# 05_Seven_Seg.net
KiCad netlist of a schematic drawn in Altium Designer
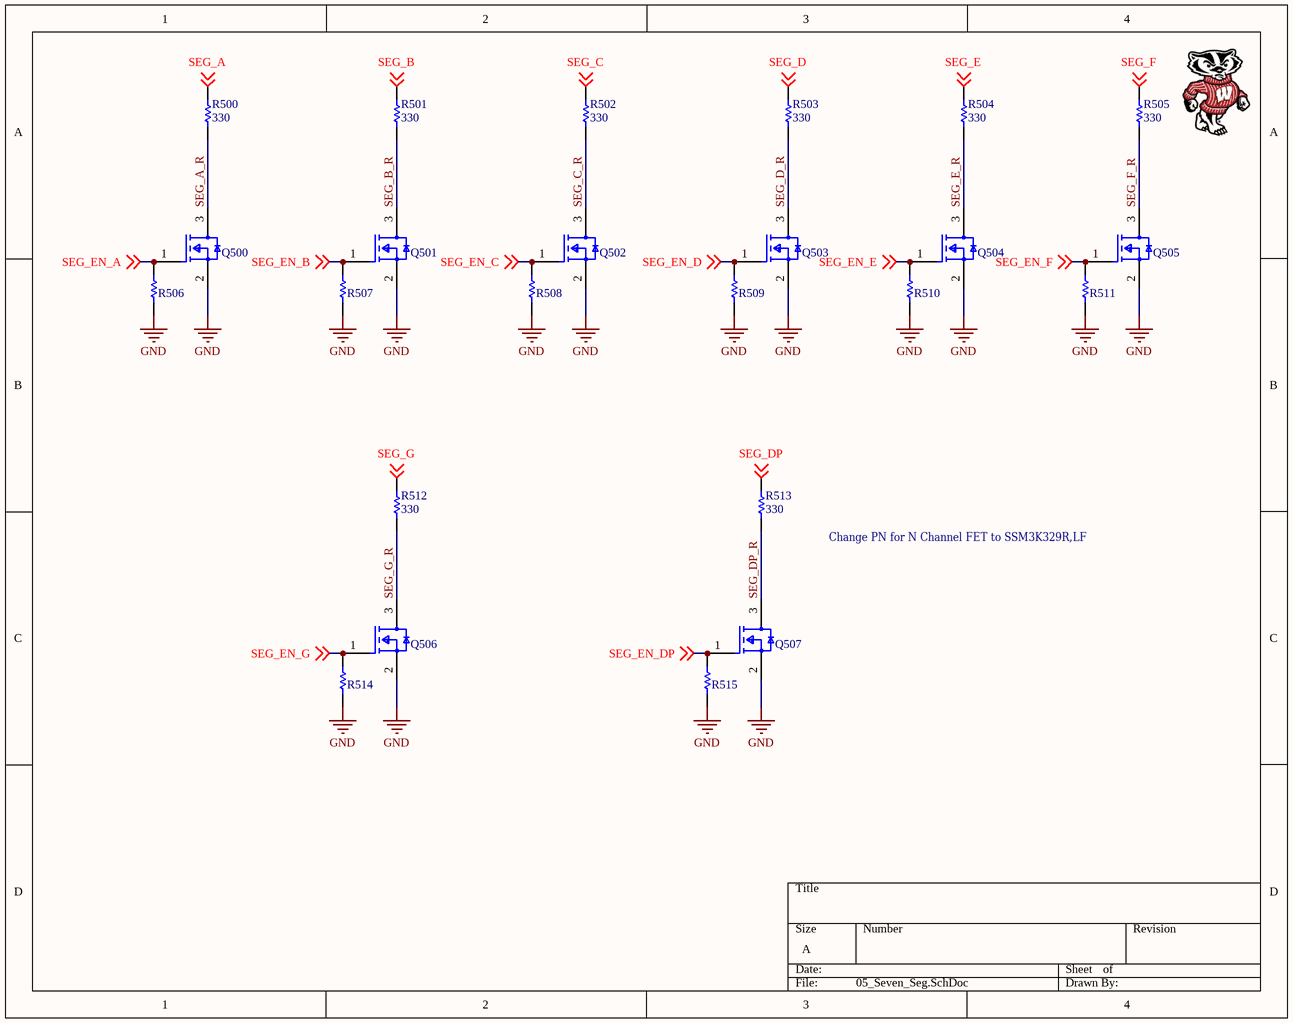
[diagram p0: 05_Seven_Seg.SchDoc]

(export (version "E")
  (design (tool "Eeschema 10.0.6"))
  (components
    (comp (ref "Q500")
      (value "NDS7002A")
      (footprint "Diodes_Inc_SOT23_IPC_A")
      (description "FAIRCHILD SEMICONDUCTOR         NDS7002A.            MOSFET, FULL REEL")
      (fields (field (name "VOLTAGE") "60V"))
      (libsource (lib "Transistors") (part "NDS7002A"))
    )
    (comp (ref "Q501")
      (value "NDS7002A")
      (footprint "Diodes_Inc_SOT23_IPC_A")
      (description "FAIRCHILD SEMICONDUCTOR         NDS7002A.            MOSFET, FULL REEL")
      (fields (field (name "VOLTAGE") "60V"))
      (libsource (lib "Transistors") (part "NDS7002A"))
    )
    (comp (ref "Q502")
      (value "NDS7002A")
      (footprint "Diodes_Inc_SOT23_IPC_A")
      (description "FAIRCHILD SEMICONDUCTOR         NDS7002A.            MOSFET, FULL REEL")
      (fields (field (name "VOLTAGE") "60V"))
      (libsource (lib "Transistors") (part "NDS7002A"))
    )
    (comp (ref "Q503")
      (value "NDS7002A")
      (footprint "Diodes_Inc_SOT23_IPC_A")
      (description "FAIRCHILD SEMICONDUCTOR         NDS7002A.            MOSFET, FULL REEL")
      (fields (field (name "VOLTAGE") "60V"))
      (libsource (lib "Transistors") (part "NDS7002A"))
    )
    (comp (ref "Q504")
      (value "NDS7002A")
      (footprint "Diodes_Inc_SOT23_IPC_A")
      (description "FAIRCHILD SEMICONDUCTOR         NDS7002A.            MOSFET, FULL REEL")
      (fields (field (name "VOLTAGE") "60V"))
      (libsource (lib "Transistors") (part "NDS7002A"))
    )
    (comp (ref "Q505")
      (value "NDS7002A")
      (footprint "Diodes_Inc_SOT23_IPC_A")
      (description "FAIRCHILD SEMICONDUCTOR         NDS7002A.            MOSFET, FULL REEL")
      (fields (field (name "VOLTAGE") "60V"))
      (libsource (lib "Transistors") (part "NDS7002A"))
    )
    (comp (ref "Q506")
      (value "NDS7002A")
      (footprint "Diodes_Inc_SOT23_IPC_A")
      (description "FAIRCHILD SEMICONDUCTOR         NDS7002A.            MOSFET, FULL REEL")
      (fields (field (name "VOLTAGE") "60V"))
      (libsource (lib "Transistors") (part "NDS7002A"))
    )
    (comp (ref "Q507")
      (value "NDS7002A")
      (footprint "Diodes_Inc_SOT23_IPC_A")
      (description "FAIRCHILD SEMICONDUCTOR         NDS7002A.            MOSFET, FULL REEL")
      (fields (field (name "VOLTAGE") "60V"))
      (libsource (lib "Transistors") (part "NDS7002A"))
    )
    (comp (ref "R500")
      (value "330")
      (footprint "RES_0805")
      (description "RES 330 OHM 1% 1/8W 0805")
      (fields (field (name "TOLERANCE") "1%"))
      (libsource (lib "Resistors") (part "RES_0805_R_330.00"))
    )
    (comp (ref "R501")
      (value "330")
      (footprint "RES_0805")
      (description "RES 330 OHM 1% 1/8W 0805")
      (fields (field (name "TOLERANCE") "1%"))
      (libsource (lib "Resistors") (part "RES_0805_R_330.00"))
    )
    (comp (ref "R502")
      (value "330")
      (footprint "RES_0805")
      (description "RES 330 OHM 1% 1/8W 0805")
      (fields (field (name "TOLERANCE") "1%"))
      (libsource (lib "Resistors") (part "RES_0805_R_330.00"))
    )
    (comp (ref "R503")
      (value "330")
      (footprint "RES_0805")
      (description "RES 330 OHM 1% 1/8W 0805")
      (fields (field (name "TOLERANCE") "1%"))
      (libsource (lib "Resistors") (part "RES_0805_R_330.00"))
    )
    (comp (ref "R504")
      (value "330")
      (footprint "RES_0805")
      (description "RES 330 OHM 1% 1/8W 0805")
      (fields (field (name "TOLERANCE") "1%"))
      (libsource (lib "Resistors") (part "RES_0805_R_330.00"))
    )
    (comp (ref "R505")
      (value "330")
      (footprint "RES_0805")
      (description "RES 330 OHM 1% 1/8W 0805")
      (fields (field (name "TOLERANCE") "1%"))
      (libsource (lib "Resistors") (part "RES_0805_R_330.00"))
    )
    (comp (ref "R506")
      (value "RES_0805_K_010.00")
      (footprint "RES_0805")
      (description "RES SMD 10K OHM 1% 1/8W 0805")
      (fields (field (name "TOLERANCE") "1%"))
      (libsource (lib "Resistors") (part "RES_0805_K_010.00"))
    )
    (comp (ref "R507")
      (value "RES_0805_K_010.00")
      (footprint "RES_0805")
      (description "RES SMD 10K OHM 1% 1/8W 0805")
      (fields (field (name "TOLERANCE") "1%"))
      (libsource (lib "Resistors") (part "RES_0805_K_010.00"))
    )
    (comp (ref "R508")
      (value "RES_0805_K_010.00")
      (footprint "RES_0805")
      (description "RES SMD 10K OHM 1% 1/8W 0805")
      (fields (field (name "TOLERANCE") "1%"))
      (libsource (lib "Resistors") (part "RES_0805_K_010.00"))
    )
    (comp (ref "R509")
      (value "RES_0805_K_010.00")
      (footprint "RES_0805")
      (description "RES SMD 10K OHM 1% 1/8W 0805")
      (fields (field (name "TOLERANCE") "1%"))
      (libsource (lib "Resistors") (part "RES_0805_K_010.00"))
    )
    (comp (ref "R510")
      (value "RES_0805_K_010.00")
      (footprint "RES_0805")
      (description "RES SMD 10K OHM 1% 1/8W 0805")
      (fields (field (name "TOLERANCE") "1%"))
      (libsource (lib "Resistors") (part "RES_0805_K_010.00"))
    )
    (comp (ref "R511")
      (value "RES_0805_K_010.00")
      (footprint "RES_0805")
      (description "RES SMD 10K OHM 1% 1/8W 0805")
      (fields (field (name "TOLERANCE") "1%"))
      (libsource (lib "Resistors") (part "RES_0805_K_010.00"))
    )
    (comp (ref "R512")
      (value "330")
      (footprint "RES_0805")
      (description "RES 330 OHM 1% 1/8W 0805")
      (fields (field (name "TOLERANCE") "1%"))
      (libsource (lib "Resistors") (part "RES_0805_R_330.00"))
    )
    (comp (ref "R513")
      (value "330")
      (footprint "RES_0805")
      (description "RES 330 OHM 1% 1/8W 0805")
      (fields (field (name "TOLERANCE") "1%"))
      (libsource (lib "Resistors") (part "RES_0805_R_330.00"))
    )
    (comp (ref "R514")
      (value "RES_0805_K_010.00")
      (footprint "RES_0805")
      (description "RES SMD 10K OHM 1% 1/8W 0805")
      (fields (field (name "TOLERANCE") "1%"))
      (libsource (lib "Resistors") (part "RES_0805_K_010.00"))
    )
    (comp (ref "R515")
      (value "RES_0805_K_010.00")
      (footprint "RES_0805")
      (description "RES SMD 10K OHM 1% 1/8W 0805")
      (fields (field (name "TOLERANCE") "1%"))
      (libsource (lib "Resistors") (part "RES_0805_K_010.00"))
    )
  )
  (nets
    (net (code "1") (name "/SEG_A_R") (class "Default")
      (node (ref "Q500") (pin "3") (pinfunction "D_3") (pintype "passive"))
      (node (ref "R500") (pin "1") (pinfunction "1_1") (pintype "passive"))
    )
    (net (code "2") (name "/SEG_B_R") (class "Default")
      (node (ref "Q501") (pin "3") (pinfunction "D_3") (pintype "passive"))
      (node (ref "R501") (pin "1") (pinfunction "1_1") (pintype "passive"))
    )
    (net (code "3") (name "/SEG_C_R") (class "Default")
      (node (ref "Q502") (pin "3") (pinfunction "D_3") (pintype "passive"))
      (node (ref "R502") (pin "1") (pinfunction "1_1") (pintype "passive"))
    )
    (net (code "4") (name "/SEG_DP_R") (class "Default")
      (node (ref "Q507") (pin "3") (pinfunction "D_3") (pintype "passive"))
      (node (ref "R513") (pin "1") (pinfunction "1_1") (pintype "passive"))
    )
    (net (code "5") (name "/SEG_D_R") (class "Default")
      (node (ref "Q503") (pin "3") (pinfunction "D_3") (pintype "passive"))
      (node (ref "R503") (pin "1") (pinfunction "1_1") (pintype "passive"))
    )
    (net (code "6") (name "/SEG_E_R") (class "Default")
      (node (ref "Q504") (pin "3") (pinfunction "D_3") (pintype "passive"))
      (node (ref "R504") (pin "1") (pinfunction "1_1") (pintype "passive"))
    )
    (net (code "7") (name "/SEG_F_R") (class "Default")
      (node (ref "Q505") (pin "3") (pinfunction "D_3") (pintype "passive"))
      (node (ref "R505") (pin "1") (pinfunction "1_1") (pintype "passive"))
    )
    (net (code "8") (name "/SEG_G_R") (class "Default")
      (node (ref "Q506") (pin "3") (pinfunction "D_3") (pintype "passive"))
      (node (ref "R512") (pin "1") (pinfunction "1_1") (pintype "passive"))
    )
    (net (code "9") (name "GND") (class "Default")
      (node (ref "Q500") (pin "2") (pinfunction "S_2") (pintype "passive"))
      (node (ref "Q501") (pin "2") (pinfunction "S_2") (pintype "passive"))
      (node (ref "Q502") (pin "2") (pinfunction "S_2") (pintype "passive"))
      (node (ref "Q503") (pin "2") (pinfunction "S_2") (pintype "passive"))
      (node (ref "Q504") (pin "2") (pinfunction "S_2") (pintype "passive"))
      (node (ref "Q505") (pin "2") (pinfunction "S_2") (pintype "passive"))
      (node (ref "Q506") (pin "2") (pinfunction "S_2") (pintype "passive"))
      (node (ref "Q507") (pin "2") (pinfunction "S_2") (pintype "passive"))
      (node (ref "R506") (pin "1") (pinfunction "1_1") (pintype "passive"))
      (node (ref "R507") (pin "1") (pinfunction "1_1") (pintype "passive"))
      (node (ref "R508") (pin "1") (pinfunction "1_1") (pintype "passive"))
      (node (ref "R509") (pin "1") (pinfunction "1_1") (pintype "passive"))
      (node (ref "R510") (pin "1") (pinfunction "1_1") (pintype "passive"))
      (node (ref "R511") (pin "1") (pinfunction "1_1") (pintype "passive"))
      (node (ref "R514") (pin "1") (pinfunction "1_1") (pintype "passive"))
      (node (ref "R515") (pin "1") (pinfunction "1_1") (pintype "passive"))
    )
    (net (code "10") (name "SEG_A") (class "Default")
      (node (ref "R500") (pin "2") (pinfunction "2_2") (pintype "passive"))
    )
    (net (code "11") (name "SEG_B") (class "Default")
      (node (ref "R501") (pin "2") (pinfunction "2_2") (pintype "passive"))
    )
    (net (code "12") (name "SEG_C") (class "Default")
      (node (ref "R502") (pin "2") (pinfunction "2_2") (pintype "passive"))
    )
    (net (code "13") (name "SEG_D") (class "Default")
      (node (ref "R503") (pin "2") (pinfunction "2_2") (pintype "passive"))
    )
    (net (code "14") (name "SEG_DP") (class "Default")
      (node (ref "R513") (pin "2") (pinfunction "2_2") (pintype "passive"))
    )
    (net (code "15") (name "SEG_E") (class "Default")
      (node (ref "R504") (pin "2") (pinfunction "2_2") (pintype "passive"))
    )
    (net (code "16") (name "SEG_EN_A") (class "Default")
      (node (ref "Q500") (pin "1") (pinfunction "G_1") (pintype "passive"))
      (node (ref "R506") (pin "2") (pinfunction "2_2") (pintype "passive"))
    )
    (net (code "17") (name "SEG_EN_B") (class "Default")
      (node (ref "Q501") (pin "1") (pinfunction "G_1") (pintype "passive"))
      (node (ref "R507") (pin "2") (pinfunction "2_2") (pintype "passive"))
    )
    (net (code "18") (name "SEG_EN_C") (class "Default")
      (node (ref "Q502") (pin "1") (pinfunction "G_1") (pintype "passive"))
      (node (ref "R508") (pin "2") (pinfunction "2_2") (pintype "passive"))
    )
    (net (code "19") (name "SEG_EN_D") (class "Default")
      (node (ref "Q503") (pin "1") (pinfunction "G_1") (pintype "passive"))
      (node (ref "R509") (pin "2") (pinfunction "2_2") (pintype "passive"))
    )
    (net (code "20") (name "SEG_EN_DP") (class "Default")
      (node (ref "Q507") (pin "1") (pinfunction "G_1") (pintype "passive"))
      (node (ref "R515") (pin "2") (pinfunction "2_2") (pintype "passive"))
    )
    (net (code "21") (name "SEG_EN_E") (class "Default")
      (node (ref "Q504") (pin "1") (pinfunction "G_1") (pintype "passive"))
      (node (ref "R510") (pin "2") (pinfunction "2_2") (pintype "passive"))
    )
    (net (code "22") (name "SEG_EN_F") (class "Default")
      (node (ref "Q505") (pin "1") (pinfunction "G_1") (pintype "passive"))
      (node (ref "R511") (pin "2") (pinfunction "2_2") (pintype "passive"))
    )
    (net (code "23") (name "SEG_EN_G") (class "Default")
      (node (ref "Q506") (pin "1") (pinfunction "G_1") (pintype "passive"))
      (node (ref "R514") (pin "2") (pinfunction "2_2") (pintype "passive"))
    )
    (net (code "24") (name "SEG_F") (class "Default")
      (node (ref "R505") (pin "2") (pinfunction "2_2") (pintype "passive"))
    )
    (net (code "25") (name "SEG_G") (class "Default")
      (node (ref "R512") (pin "2") (pinfunction "2_2") (pintype "passive"))
    )
  )
)
